# Matching_Network.net
KiCad netlist of a schematic drawn in Altium Designer
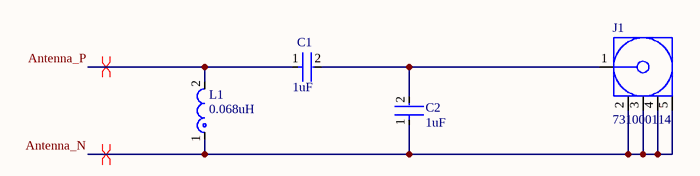
[diagram p0: Matching_Network.SchDoc]

(export (version "E")
  (design (tool "Eeschema 10.0.6"))
  (components
    (comp (ref "C1")
      (value "1uF")
      (footprint "FP-C0603C-CF-MFG")
      (description "C0603 0.10 μF X7R 30ppm/°C 10.00% 50 V")
      (fields (field (name "TOLERANCE") "0.1"))
      (libsource (lib "Altium Content Vault") (part "b4654b650e69147ec39a6b967a45e02"))
    )
    (comp (ref "C2")
      (value "1uF")
      (footprint "FP-C0603C-CF-MFG")
      (description "C0603 0.10 μF X7R 30ppm/°C 10.00% 50 V")
      (fields (field (name "TOLERANCE") "0.1"))
      (libsource (lib "Altium Content Vault") (part "b4654b650e69147ec39a6b967a45e02"))
    )
    (comp (ref "J1")
      (value "731000114")
      (footprint "MOLX-731000114_V")
      (description "SMA Right-Angle PCB Jack Receptacle, Brass Body, Gold Plated, 50 Ohm, 5-Pin THD, RoHS, Tray")
      (fields (field (name "MANUFACTURER") "Molex"))
      (libsource (lib "Altium Content Vault") (part "CN-S-4F-RF5"))
    )
    (comp (ref "L1")
      (value "0.068uH")
      (footprint "FP-LQG18HH_00-MFG")
      (description "Multilayer type RF Inductor 68nH ±5% 0.8Ω 400mA 0603")
      (fields (field (name "TOLERANCE") "5%"))
      (libsource (lib "Altium Content Vault") (part "4cc4b267dca4c8e51f7102f422741d8"))
    )
  )
  (nets
    (net (code "1") (name "/Antenna_N") (class "Default")
      (node (ref "C2") (pin "1") (pinfunction "1_1") (pintype "passive"))
      (node (ref "J1") (pin "2") (pinfunction "2_2") (pintype "passive"))
      (node (ref "J1") (pin "3") (pinfunction "3_3") (pintype "passive"))
      (node (ref "J1") (pin "4") (pinfunction "4_4") (pintype "passive"))
      (node (ref "J1") (pin "5") (pinfunction "5_5") (pintype "passive"))
      (node (ref "L1") (pin "1") (pinfunction "1_1") (pintype "passive"))
    )
    (net (code "2") (name "/Antenna_P") (class "Default")
      (node (ref "C1") (pin "1") (pinfunction "1_1") (pintype "passive"))
      (node (ref "L1") (pin "2") (pinfunction "2_2") (pintype "passive"))
    )
    (net (code "3") (name "Net-(C1-Pad2)") (class "Default")
      (node (ref "C1") (pin "2") (pinfunction "2_2") (pintype "passive"))
      (node (ref "C2") (pin "2") (pinfunction "2_2") (pintype "passive"))
      (node (ref "J1") (pin "1") (pinfunction "1_1") (pintype "passive"))
    )
  )
)
